# Fuel_Gauge.net
KiCad netlist of a schematic drawn in Altium Designer
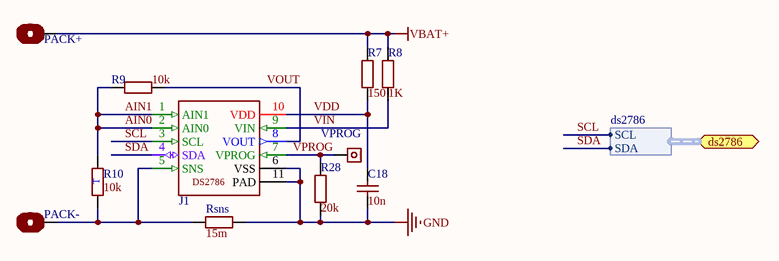
[diagram p0: Fuel Gauge.SchDoc]

(export (version "E")
  (design (tool "Eeschema 10.0.6"))
  (components
    (comp (ref "C18")
      (value "10n")
      (footprint "C0402_h")
      (description "Capacitor")
      (fields (field (name "PUBLISHER") "Altium Limited"))
      (libsource (lib "电子元件封装库") (part "贴片电容-无极性"))
    )
    (comp (ref "J1")
      (value "DS2786G+")
      (footprint "TDFN-EP-10")
      (description "Fuek Gauge")
      (fields (field (name "DIGIKEYPARTNUMBER") "DS2786G+-ND"))
      (libsource (lib "电子元件封装库") (part "DS2786G+"))
    )
    (comp (ref "PACK+")
      (value "Pad")
      (footprint "PAD")
      (description "PAD")
      (libsource (lib "接插器件封装库") (part "Pad"))
    )
    (comp (ref "PACK-")
      (value "Pad")
      (footprint "PAD")
      (description "PAD")
      (libsource (lib "接插器件封装库") (part "Pad"))
    )
    (comp (ref "R7")
      (value "150")
      (footprint "R0402")
      (description "Register")
      (libsource (lib "电子元件封装库") (part "贴片电阻"))
    )
    (comp (ref "R8")
      (value "1K")
      (footprint "R0402")
      (description "Register")
      (libsource (lib "电子元件封装库") (part "贴片电阻"))
    )
    (comp (ref "R9")
      (value "10k")
      (footprint "R0402")
      (description "Register")
      (libsource (lib "") (part "贴片电阻_2"))
    )
    (comp (ref "R10")
      (value "10k")
      (footprint "NTC")
      (description "Register")
      (libsource (lib "电子元件封装库") (part "热敏电阻"))
    )
    (comp (ref "R28")
      (value "20k")
      (footprint "R0402")
      (description "Register")
      (libsource (lib "电子元件封装库") (part "贴片电阻"))
    )
    (comp (ref "Rsns")
      (value "15m")
      (footprint "R0805")
      (description "Register")
      (libsource (lib "") (part "贴片电阻_1"))
    )
    (comp (ref "VPROG")
      (value "TestPoint")
      (footprint "TestPoint")
      (libsource (lib "电子元件封装库") (part "TestPoint"))
    )
  )
  (nets
    (net (code "2") (name "/AIN0") (class "Default")
      (node (ref "J1") (pin "1") (pinfunction "AIN1_1") (pintype "input"))
      (node (ref "J1") (pin "2") (pinfunction "AIN0_2") (pintype "input"))
      (node (ref "R10") (pin "2") (pinfunction "2_2") (pintype "passive"))
      (node (ref "R9") (pin "2") (pinfunction "2_2") (pintype "passive"))
    )
    (net (code "3") (name "/SCL") (class "Default")
      (node (ref "J1") (pin "3") (pinfunction "SCL_3") (pintype "input"))
    )
    (net (code "4") (name "/SDA") (class "Default")
      (node (ref "J1") (pin "4") (pinfunction "SDA_4") (pintype "bidirectional"))
    )
    (net (code "5") (name "/VDD") (class "Default")
      (node (ref "C18") (pin "2") (pinfunction "2_2") (pintype "passive"))
      (node (ref "J1") (pin "10") (pinfunction "VDD_10") (pintype "power_in"))
      (node (ref "R7") (pin "2") (pinfunction "2_2") (pintype "passive"))
    )
    (net (code "6") (name "/VIN") (class "Default")
      (node (ref "J1") (pin "9") (pinfunction "VIN_9") (pintype "input"))
      (node (ref "R8") (pin "2") (pinfunction "2_2") (pintype "passive"))
    )
    (net (code "7") (name "/VOUT") (class "Default")
      (node (ref "J1") (pin "8") (pinfunction "VOUT_8") (pintype "output"))
      (node (ref "R9") (pin "1") (pinfunction "1_1") (pintype "passive"))
    )
    (net (code "8") (name "/VPROG") (class "Default")
      (node (ref "J1") (pin "7") (pinfunction "VPROG_7") (pintype "input"))
      (node (ref "R28") (pin "1") (pinfunction "1_1") (pintype "passive"))
      (node (ref "VPROG") (pin "1") (pinfunction "test_1") (pintype "passive"))
    )
    (net (code "10") (name "GND") (class "Default")
      (node (ref "C18") (pin "1") (pinfunction "1_1") (pintype "passive"))
      (node (ref "J1") (pin "11") (pinfunction "PAD_11") (pintype "passive"))
      (node (ref "J1") (pin "6") (pinfunction "VSS_6") (pintype "power_in"))
      (node (ref "R28") (pin "2") (pinfunction "2_2") (pintype "passive"))
      (node (ref "Rsns") (pin "2") (pinfunction "2_2") (pintype "passive"))
    )
    (net (code "11") (name "Net-(J1-SNS)") (class "Default")
      (node (ref "J1") (pin "5") (pinfunction "SNS_5") (pintype "input"))
      (node (ref "PACK-") (pin "1") (pinfunction "1_1") (pintype "passive"))
      (node (ref "R10") (pin "1") (pinfunction "1_1") (pintype "passive"))
      (node (ref "Rsns") (pin "1") (pinfunction "1_1") (pintype "passive"))
    )
    (net (code "12") (name "VBAT+") (class "Default")
      (node (ref "PACK+") (pin "1") (pinfunction "1_1") (pintype "passive"))
      (node (ref "R7") (pin "1") (pinfunction "1_1") (pintype "passive"))
      (node (ref "R8") (pin "1") (pinfunction "1_1") (pintype "passive"))
    )
  )
)
